# PIDRegler.net
KiCad netlist of a schematic drawn in EAGLE
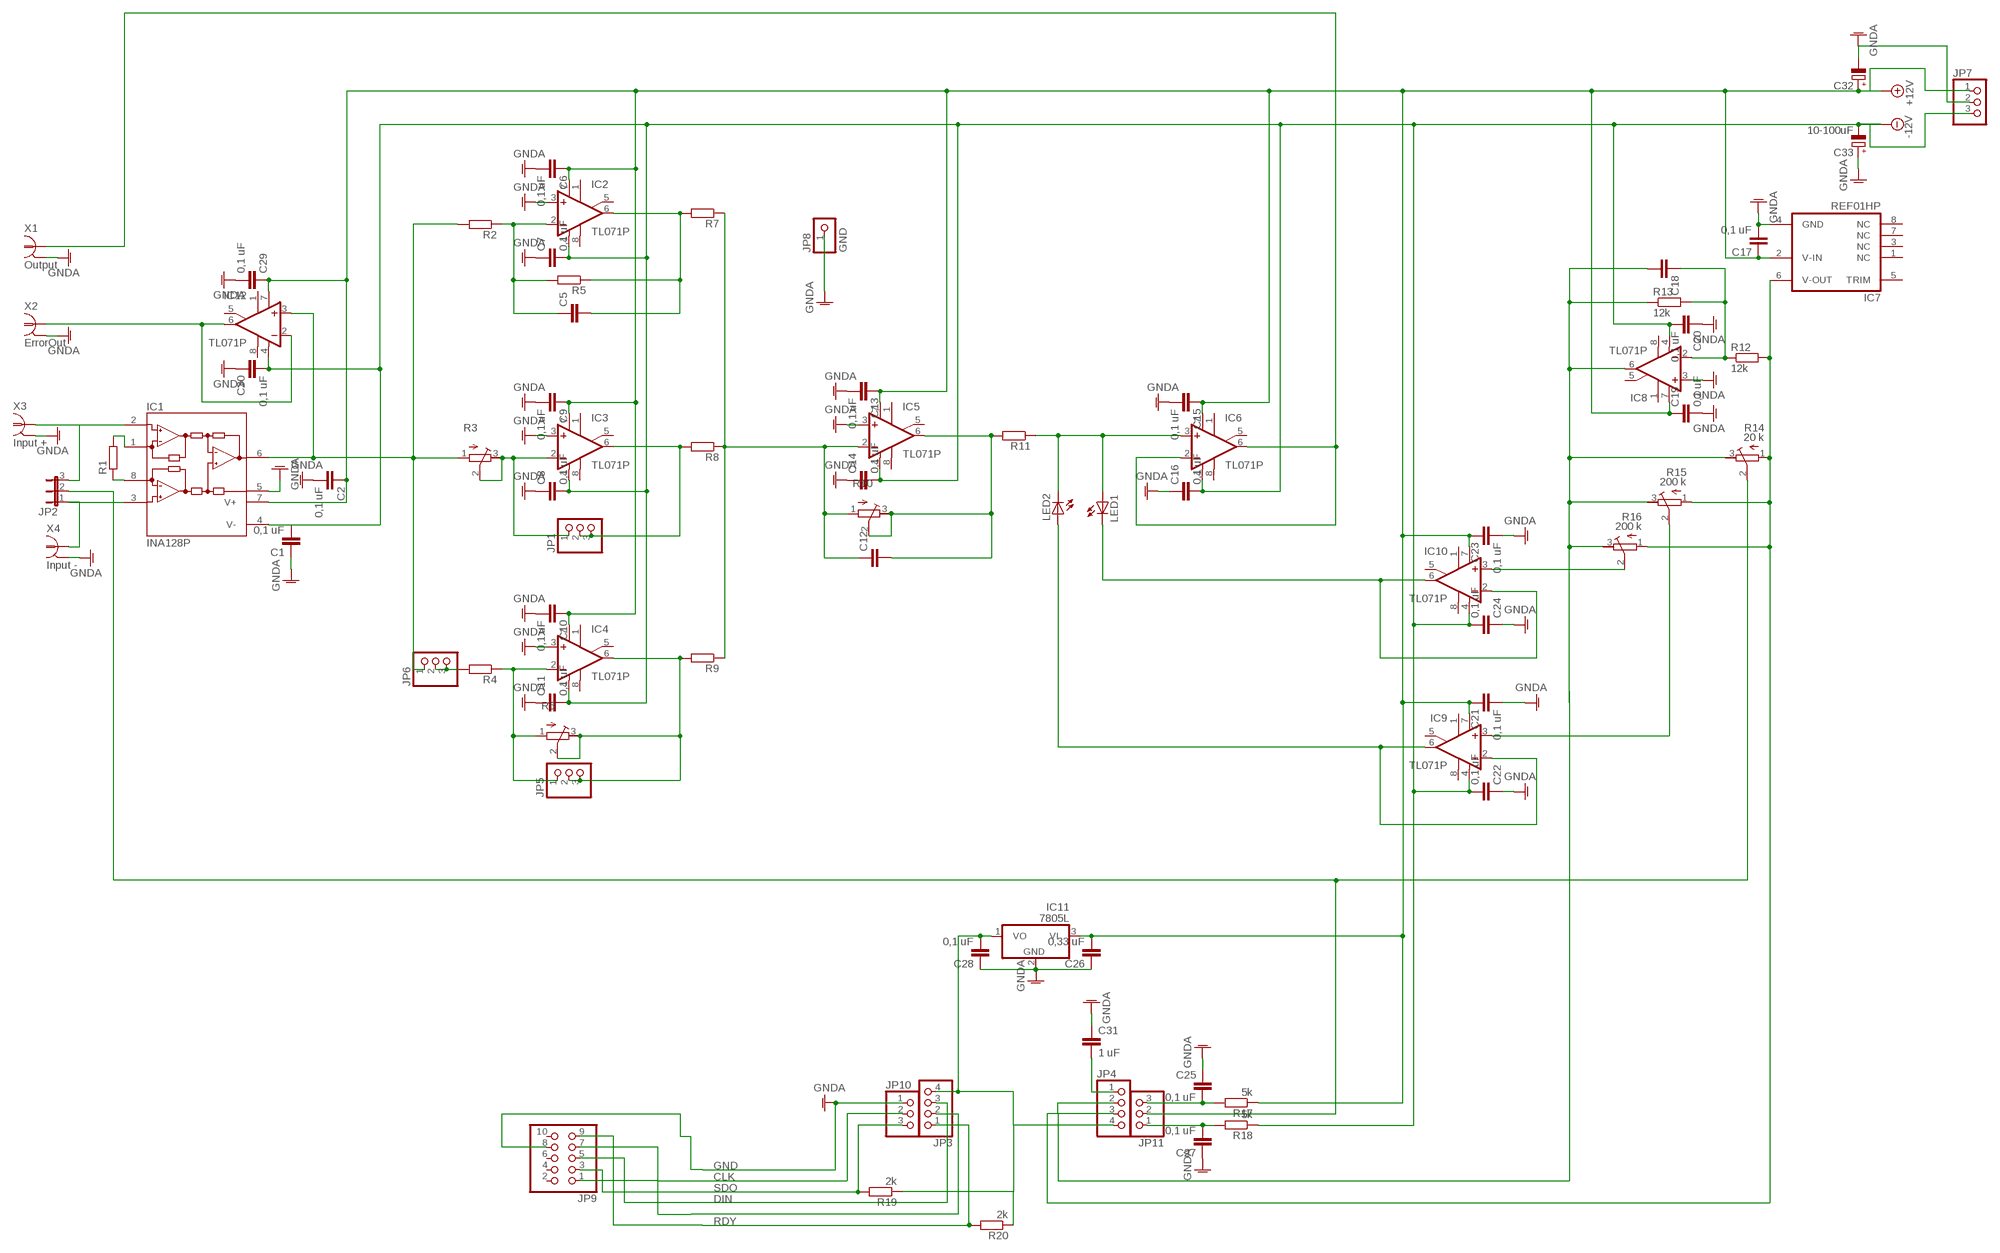
[diagram p0: schematic, sheet 1]

(export (version "E")
  (design (tool "Eeschema 10.0.6"))
  (components
    (comp (ref "C1")
      (value "0,1 uF")
      (footprint "eagle-import:C1206")
      (libsource (lib "eagle-import") (part "C-EUC1206"))
    )
    (comp (ref "C2")
      (value "0,1 uF")
      (footprint "eagle-import:C1206")
      (libsource (lib "eagle-import") (part "C-EUC1206"))
    )
    (comp (ref "C5")
      (value "C-EUC1206")
      (footprint "eagle-import:C1206")
      (libsource (lib "eagle-import") (part "C-EUC1206"))
    )
    (comp (ref "C6")
      (value "0,1 uF")
      (footprint "eagle-import:C1206")
      (libsource (lib "eagle-import") (part "C-EUC1206"))
    )
    (comp (ref "C7")
      (value "0,1 uF")
      (footprint "eagle-import:C1206")
      (libsource (lib "eagle-import") (part "C-EUC1206"))
    )
    (comp (ref "C8")
      (value "0,1 uF")
      (footprint "eagle-import:C1206")
      (libsource (lib "eagle-import") (part "C-EUC1206"))
    )
    (comp (ref "C9")
      (value "0,1 uF")
      (footprint "eagle-import:C1206")
      (libsource (lib "eagle-import") (part "C-EUC1206"))
    )
    (comp (ref "C10")
      (value "0,1 uF")
      (footprint "eagle-import:C1206")
      (libsource (lib "eagle-import") (part "C-EUC1206"))
    )
    (comp (ref "C11")
      (value "0,1 uF")
      (footprint "eagle-import:C1206")
      (libsource (lib "eagle-import") (part "C-EUC1206"))
    )
    (comp (ref "C12")
      (value "C-EUC1206")
      (footprint "eagle-import:C1206")
      (libsource (lib "eagle-import") (part "C-EUC1206"))
    )
    (comp (ref "C13")
      (value "0,1 uF")
      (footprint "eagle-import:C1206")
      (libsource (lib "eagle-import") (part "C-EUC1206"))
    )
    (comp (ref "C14")
      (value "0,1 uF")
      (footprint "eagle-import:C1206")
      (libsource (lib "eagle-import") (part "C-EUC1206"))
    )
    (comp (ref "C15")
      (value "0,1 uF")
      (footprint "eagle-import:C1206")
      (libsource (lib "eagle-import") (part "C-EUC1206"))
    )
    (comp (ref "C16")
      (value "0,1 uF")
      (footprint "eagle-import:C1206")
      (libsource (lib "eagle-import") (part "C-EUC1206"))
    )
    (comp (ref "C17")
      (value "0,1 uF")
      (footprint "eagle-import:C1206")
      (libsource (lib "eagle-import") (part "C-EUC1206"))
    )
    (comp (ref "C18")
      (value "C-EUC1206")
      (footprint "eagle-import:C1206")
      (libsource (lib "eagle-import") (part "C-EUC1206"))
    )
    (comp (ref "C19")
      (value "0,1 uF")
      (footprint "eagle-import:C1206")
      (libsource (lib "eagle-import") (part "C-EUC1206"))
    )
    (comp (ref "C20")
      (value "0,1 uF")
      (footprint "eagle-import:C1206")
      (libsource (lib "eagle-import") (part "C-EUC1206"))
    )
    (comp (ref "C21")
      (value "0,1 uF")
      (footprint "eagle-import:C1206")
      (libsource (lib "eagle-import") (part "C-EUC1206"))
    )
    (comp (ref "C22")
      (value "0,1 uF")
      (footprint "eagle-import:C1206")
      (libsource (lib "eagle-import") (part "C-EUC1206"))
    )
    (comp (ref "C23")
      (value "0,1 uF")
      (footprint "eagle-import:C1206")
      (libsource (lib "eagle-import") (part "C-EUC1206"))
    )
    (comp (ref "C24")
      (value "0,1 uF")
      (footprint "eagle-import:C1206")
      (libsource (lib "eagle-import") (part "C-EUC1206"))
    )
    (comp (ref "C25")
      (value "0,1 uF")
      (footprint "eagle-import:C1206")
      (libsource (lib "eagle-import") (part "C-EUC1206"))
    )
    (comp (ref "C26")
      (value "0,33 uF")
      (footprint "eagle-import:C1206")
      (libsource (lib "eagle-import") (part "C-EUC1206"))
    )
    (comp (ref "C27")
      (value "0,1 uF")
      (footprint "eagle-import:C1206")
      (libsource (lib "eagle-import") (part "C-EUC1206"))
    )
    (comp (ref "C28")
      (value "0,1 uF")
      (footprint "eagle-import:C1206")
      (libsource (lib "eagle-import") (part "C-EUC1206"))
    )
    (comp (ref "C29")
      (value "0,1 uF")
      (footprint "eagle-import:C1206")
      (libsource (lib "eagle-import") (part "C-EUC1206"))
    )
    (comp (ref "C30")
      (value "0,1 uF")
      (footprint "eagle-import:C1206")
      (libsource (lib "eagle-import") (part "C-EUC1206"))
    )
    (comp (ref "C31")
      (value "1 uF")
      (footprint "eagle-import:C1206")
      (libsource (lib "eagle-import") (part "C-EUC1206"))
    )
    (comp (ref "C32")
      (value "CPOL-EUE2.5-6")
      (footprint "eagle-import:E2,5-6")
      (libsource (lib "eagle-import") (part "CPOL-EUE2.5-6"))
    )
    (comp (ref "C33")
      (value "10-100uF")
      (footprint "eagle-import:E2,5-6")
      (libsource (lib "eagle-import") (part "CPOL-EUE2.5-6"))
    )
    (comp (ref "IC1")
      (value "INA128P")
      (footprint "eagle-import:DIL08")
      (fields (field (name "MF") "TEXAS INSTRUMENTS"))
      (libsource (lib "eagle-import") (part "INA128P"))
    )
    (comp (ref "IC2")
      (value "TL071P")
      (footprint "eagle-import:DIL08")
      (libsource (lib "eagle-import") (part "TL071P"))
    )
    (comp (ref "IC3")
      (value "TL071P")
      (footprint "eagle-import:DIL08")
      (libsource (lib "eagle-import") (part "TL071P"))
    )
    (comp (ref "IC4")
      (value "TL071P")
      (footprint "eagle-import:DIL08")
      (libsource (lib "eagle-import") (part "TL071P"))
    )
    (comp (ref "IC5")
      (value "TL071P")
      (footprint "eagle-import:DIL08")
      (libsource (lib "eagle-import") (part "TL071P"))
    )
    (comp (ref "IC6")
      (value "TL071P")
      (footprint "eagle-import:DIL08")
      (libsource (lib "eagle-import") (part "TL071P"))
    )
    (comp (ref "IC7")
      (value "REF01HP")
      (footprint "eagle-import:DIL08")
      (fields (field (name "MF") "ALTERA CORPORATION"))
      (libsource (lib "eagle-import") (part "REF01HP"))
    )
    (comp (ref "IC8")
      (value "TL071P")
      (footprint "eagle-import:DIL08")
      (libsource (lib "eagle-import") (part "TL071P"))
    )
    (comp (ref "IC9")
      (value "TL071P")
      (footprint "eagle-import:DIL08")
      (libsource (lib "eagle-import") (part "TL071P"))
    )
    (comp (ref "IC10")
      (value "TL071P")
      (footprint "eagle-import:DIL08")
      (libsource (lib "eagle-import") (part "TL071P"))
    )
    (comp (ref "IC11")
      (value "7805L")
      (footprint "eagle-import:TO92")
      (libsource (lib "eagle-import") (part "78L05"))
    )
    (comp (ref "IC12")
      (value "TL071P")
      (footprint "eagle-import:DIL08")
      (libsource (lib "eagle-import") (part "TL071P"))
    )
    (comp (ref "JP1")
      (value "PINHD-1X3")
      (footprint "eagle-import:1X03")
      (libsource (lib "eagle-import") (part "PINHD-1X3"))
    )
    (comp (ref "JP2")
      (value "JP2E")
      (footprint "eagle-import:JP2")
      (libsource (lib "eagle-import") (part "JP2E"))
    )
    (comp (ref "JP3")
      (value "PINHD-1X4")
      (footprint "eagle-import:1X04")
      (libsource (lib "eagle-import") (part "PINHD-1X4"))
    )
    (comp (ref "JP4")
      (value "PINHD-1X4")
      (footprint "eagle-import:1X04")
      (libsource (lib "eagle-import") (part "PINHD-1X4"))
    )
    (comp (ref "JP5")
      (value "PINHD-1X3")
      (footprint "eagle-import:1X03")
      (libsource (lib "eagle-import") (part "PINHD-1X3"))
    )
    (comp (ref "JP6")
      (value "PINHD-1X3")
      (footprint "eagle-import:1X03")
      (libsource (lib "eagle-import") (part "PINHD-1X3"))
    )
    (comp (ref "JP7")
      (value "PINHD-1X3")
      (footprint "eagle-import:1X03")
      (libsource (lib "eagle-import") (part "PINHD-1X3"))
    )
    (comp (ref "JP8")
      (value "GND")
      (footprint "eagle-import:1X01")
      (libsource (lib "eagle-import") (part "PINHD-1X1"))
    )
    (comp (ref "JP9")
      (value "PINHD-2X5")
      (footprint "eagle-import:2X05")
      (libsource (lib "eagle-import") (part "PINHD-2X5"))
    )
    (comp (ref "JP10")
      (value "PINHD-1X3")
      (footprint "eagle-import:1X03")
      (libsource (lib "eagle-import") (part "PINHD-1X3"))
    )
    (comp (ref "JP11")
      (value "PINHD-1X3")
      (footprint "eagle-import:1X03")
      (libsource (lib "eagle-import") (part "PINHD-1X3"))
    )
    (comp (ref "LED1")
      (value "LED5MM")
      (footprint "eagle-import:LED5MM")
      (libsource (lib "eagle-import") (part "LED5MM"))
    )
    (comp (ref "LED2")
      (value "LED5MM")
      (footprint "eagle-import:LED5MM")
      (libsource (lib "eagle-import") (part "LED5MM"))
    )
    (comp (ref "R1")
      (value "R-EU_M1206")
      (footprint "eagle-import:M1206")
      (libsource (lib "eagle-import") (part "R-EU_M1206"))
    )
    (comp (ref "R2")
      (value "R-EU_M1206")
      (footprint "eagle-import:M1206")
      (libsource (lib "eagle-import") (part "R-EU_M1206"))
    )
    (comp (ref "R3")
      (value "R-TRIMM64X")
      (footprint "eagle-import:RTRIM64X")
      (libsource (lib "eagle-import") (part "R-TRIMM64X"))
    )
    (comp (ref "R4")
      (value "R-EU_M1206")
      (footprint "eagle-import:M1206")
      (libsource (lib "eagle-import") (part "R-EU_M1206"))
    )
    (comp (ref "R5")
      (value "R-EU_M1206")
      (footprint "eagle-import:M1206")
      (libsource (lib "eagle-import") (part "R-EU_M1206"))
    )
    (comp (ref "R6")
      (value "R-TRIMM64X")
      (footprint "eagle-import:RTRIM64X")
      (libsource (lib "eagle-import") (part "R-TRIMM64X"))
    )
    (comp (ref "R7")
      (value "R-EU_M1206")
      (footprint "eagle-import:M1206")
      (libsource (lib "eagle-import") (part "R-EU_M1206"))
    )
    (comp (ref "R8")
      (value "R-EU_M1206")
      (footprint "eagle-import:M1206")
      (libsource (lib "eagle-import") (part "R-EU_M1206"))
    )
    (comp (ref "R9")
      (value "R-EU_M1206")
      (footprint "eagle-import:M1206")
      (libsource (lib "eagle-import") (part "R-EU_M1206"))
    )
    (comp (ref "R10")
      (value "R-TRIMM64X")
      (footprint "eagle-import:RTRIM64X")
      (libsource (lib "eagle-import") (part "R-TRIMM64X"))
    )
    (comp (ref "R11")
      (value "R-EU_M1206")
      (footprint "eagle-import:M1206")
      (libsource (lib "eagle-import") (part "R-EU_M1206"))
    )
    (comp (ref "R12")
      (value "12k")
      (footprint "eagle-import:M1206")
      (libsource (lib "eagle-import") (part "R-EU_M1206"))
    )
    (comp (ref "R13")
      (value "12k")
      (footprint "eagle-import:M1206")
      (libsource (lib "eagle-import") (part "R-EU_M1206"))
    )
    (comp (ref "R14")
      (value "20 k")
      (footprint "eagle-import:RTRIM64X")
      (libsource (lib "eagle-import") (part "R-TRIMM64X"))
    )
    (comp (ref "R15")
      (value "200 k")
      (footprint "eagle-import:RTRIM64X")
      (libsource (lib "eagle-import") (part "R-TRIMM64X"))
    )
    (comp (ref "R16")
      (value "200 k")
      (footprint "eagle-import:RTRIM64X")
      (libsource (lib "eagle-import") (part "R-TRIMM64X"))
    )
    (comp (ref "R17")
      (value "5k")
      (footprint "eagle-import:M1206")
      (libsource (lib "eagle-import") (part "R-EU_M1206"))
    )
    (comp (ref "R18")
      (value "5k")
      (footprint "eagle-import:M1206")
      (libsource (lib "eagle-import") (part "R-EU_M1206"))
    )
    (comp (ref "R19")
      (value "2k")
      (footprint "eagle-import:M1206")
      (libsource (lib "eagle-import") (part "R-EU_M1206"))
    )
    (comp (ref "R20")
      (value "2k")
      (footprint "eagle-import:M1206")
      (libsource (lib "eagle-import") (part "R-EU_M1206"))
    )
    (comp (ref "X1")
      (value "Output")
      (footprint "eagle-import:AMP_227161")
      (fields (field (name "MF") "TYCO ELECTRONICS") (field (name "MPN") "1-227161"))
      (libsource (lib "eagle-import") (part "?2271611--0"))
    )
    (comp (ref "X2")
      (value "ErrorOut")
      (footprint "eagle-import:AMP_227161")
      (fields (field (name "MF") "TYCO ELECTRONICS") (field (name "MPN") "1-227161"))
      (libsource (lib "eagle-import") (part "?2271611--0"))
    )
    (comp (ref "X3")
      (value "Input +")
      (footprint "eagle-import:AMP_227161")
      (fields (field (name "MF") "TYCO ELECTRONICS") (field (name "MPN") "1-227161"))
      (libsource (lib "eagle-import") (part "?2271611--0"))
    )
    (comp (ref "X4")
      (value "Input -")
      (footprint "eagle-import:AMP_227161")
      (fields (field (name "MF") "TYCO ELECTRONICS") (field (name "MPN") "1-227161"))
      (libsource (lib "eagle-import") (part "?2271611--0"))
    )
  )
  (nets
    (net (code "1") (name "+12V") (class "Default")
      (node (ref "C10") (pin "1") (pinfunction "1_1") (pintype "passive"))
      (node (ref "C13") (pin "1") (pinfunction "1_1") (pintype "passive"))
      (node (ref "C15") (pin "1") (pinfunction "1_1") (pintype "passive"))
      (node (ref "C17") (pin "1") (pinfunction "1_1") (pintype "passive"))
      (node (ref "C19") (pin "1") (pinfunction "1_1") (pintype "passive"))
      (node (ref "C2") (pin "1") (pinfunction "1_1") (pintype "passive"))
      (node (ref "C21") (pin "1") (pinfunction "1_1") (pintype "passive"))
      (node (ref "C23") (pin "1") (pinfunction "1_1") (pintype "passive"))
      (node (ref "C26") (pin "2") (pinfunction "2_2") (pintype "passive"))
      (node (ref "C29") (pin "1") (pinfunction "1_1") (pintype "passive"))
      (node (ref "C32") (pin "+") (pinfunction "+_+") (pintype "passive"))
      (node (ref "C6") (pin "1") (pinfunction "1_1") (pintype "passive"))
      (node (ref "C9") (pin "1") (pinfunction "1_1") (pintype "passive"))
      (node (ref "IC1") (pin "7") (pinfunction "V+_7") (pintype "power_in"))
      (node (ref "IC10") (pin "7") (pinfunction "V+_7") (pintype "power_in"))
      (node (ref "IC11") (pin "3") (pinfunction "VI_3") (pintype "input"))
      (node (ref "IC12") (pin "7") (pinfunction "V+_7") (pintype "power_in"))
      (node (ref "IC2") (pin "7") (pinfunction "V+_7") (pintype "power_in"))
      (node (ref "IC3") (pin "7") (pinfunction "V+_7") (pintype "power_in"))
      (node (ref "IC4") (pin "7") (pinfunction "V+_7") (pintype "power_in"))
      (node (ref "IC5") (pin "7") (pinfunction "V+_7") (pintype "power_in"))
      (node (ref "IC6") (pin "7") (pinfunction "V+_7") (pintype "power_in"))
      (node (ref "IC7") (pin "2") (pinfunction "V-IN_2") (pintype "power_in"))
      (node (ref "IC8") (pin "7") (pinfunction "V+_7") (pintype "power_in"))
      (node (ref "IC9") (pin "7") (pinfunction "V+_7") (pintype "power_in"))
      (node (ref "JP7") (pin "1") (pinfunction "1_1") (pintype "passive"))
      (node (ref "R17") (pin "1") (pinfunction "1_1") (pintype "passive"))
    )
    (net (code "2") (name "-12V") (class "Default")
      (node (ref "C1") (pin "2") (pinfunction "2_2") (pintype "passive"))
      (node (ref "C11") (pin "2") (pinfunction "2_2") (pintype "passive"))
      (node (ref "C14") (pin "2") (pinfunction "2_2") (pintype "passive"))
      (node (ref "C16") (pin "2") (pinfunction "2_2") (pintype "passive"))
      (node (ref "C20") (pin "2") (pinfunction "2_2") (pintype "passive"))
      (node (ref "C22") (pin "2") (pinfunction "2_2") (pintype "passive"))
      (node (ref "C24") (pin "2") (pinfunction "2_2") (pintype "passive"))
      (node (ref "C30") (pin "2") (pinfunction "2_2") (pintype "passive"))
      (node (ref "C33") (pin "-") (pinfunction "-_-") (pintype "passive"))
      (node (ref "C7") (pin "2") (pinfunction "2_2") (pintype "passive"))
      (node (ref "C8") (pin "2") (pinfunction "2_2") (pintype "passive"))
      (node (ref "IC1") (pin "4") (pinfunction "V-_4") (pintype "power_in"))
      (node (ref "IC10") (pin "4") (pinfunction "V-_4") (pintype "power_in"))
      (node (ref "IC12") (pin "4") (pinfunction "V-_4") (pintype "power_in"))
      (node (ref "IC2") (pin "4") (pinfunction "V-_4") (pintype "power_in"))
      (node (ref "IC3") (pin "4") (pinfunction "V-_4") (pintype "power_in"))
      (node (ref "IC4") (pin "4") (pinfunction "V-_4") (pintype "power_in"))
      (node (ref "IC5") (pin "4") (pinfunction "V-_4") (pintype "power_in"))
      (node (ref "IC6") (pin "4") (pinfunction "V-_4") (pintype "power_in"))
      (node (ref "IC8") (pin "4") (pinfunction "V-_4") (pintype "power_in"))
      (node (ref "IC9") (pin "4") (pinfunction "V-_4") (pintype "power_in"))
      (node (ref "JP7") (pin "3") (pinfunction "3_3") (pintype "passive"))
      (node (ref "R18") (pin "1") (pinfunction "1_1") (pintype "passive"))
    )
    (net (code "3") (name "/CLK") (class "Default")
      (node (ref "JP10") (pin "2") (pinfunction "2_2") (pintype "passive"))
      (node (ref "JP9") (pin "1") (pinfunction "1_1") (pintype "passive"))
    )
    (net (code "4") (name "/DIN") (class "Default")
      (node (ref "JP3") (pin "3") (pinfunction "3_3") (pintype "passive"))
      (node (ref "JP9") (pin "5") (pinfunction "5_5") (pintype "passive"))
    )
    (net (code "5") (name "/RDY") (class "Default")
      (node (ref "JP3") (pin "1") (pinfunction "1_1") (pintype "passive"))
      (node (ref "JP9") (pin "9") (pinfunction "9_9") (pintype "passive"))
      (node (ref "R20") (pin "2") (pinfunction "2_2") (pintype "passive"))
    )
    (net (code "6") (name "/SDO") (class "Default")
      (node (ref "JP10") (pin "3") (pinfunction "3_3") (pintype "passive"))
      (node (ref "JP9") (pin "3") (pinfunction "3_3") (pintype "passive"))
      (node (ref "R19") (pin "2") (pinfunction "2_2") (pintype "passive"))
    )
    (net (code "7") (name "GNDA") (class "Default")
      (node (ref "C1") (pin "1") (pinfunction "1_1") (pintype "passive"))
      (node (ref "C10") (pin "2") (pinfunction "2_2") (pintype "passive"))
      (node (ref "C11") (pin "1") (pinfunction "1_1") (pintype "passive"))
      (node (ref "C13") (pin "2") (pinfunction "2_2") (pintype "passive"))
      (node (ref "C14") (pin "1") (pinfunction "1_1") (pintype "passive"))
      (node (ref "C15") (pin "2") (pinfunction "2_2") (pintype "passive"))
      (node (ref "C16") (pin "1") (pinfunction "1_1") (pintype "passive"))
      (node (ref "C17") (pin "2") (pinfunction "2_2") (pintype "passive"))
      (node (ref "C19") (pin "2") (pinfunction "2_2") (pintype "passive"))
      (node (ref "C2") (pin "2") (pinfunction "2_2") (pintype "passive"))
      (node (ref "C20") (pin "1") (pinfunction "1_1") (pintype "passive"))
      (node (ref "C21") (pin "2") (pinfunction "2_2") (pintype "passive"))
      (node (ref "C22") (pin "1") (pinfunction "1_1") (pintype "passive"))
      (node (ref "C23") (pin "2") (pinfunction "2_2") (pintype "passive"))
      (node (ref "C24") (pin "1") (pinfunction "1_1") (pintype "passive"))
      (node (ref "C25") (pin "1") (pinfunction "1_1") (pintype "passive"))
      (node (ref "C26") (pin "1") (pinfunction "1_1") (pintype "passive"))
      (node (ref "C27") (pin "1") (pinfunction "1_1") (pintype "passive"))
      (node (ref "C28") (pin "1") (pinfunction "1_1") (pintype "passive"))
      (node (ref "C29") (pin "2") (pinfunction "2_2") (pintype "passive"))
      (node (ref "C30") (pin "1") (pinfunction "1_1") (pintype "passive"))
      (node (ref "C31") (pin "1") (pinfunction "1_1") (pintype "passive"))
      (node (ref "C32") (pin "-") (pinfunction "-_-") (pintype "passive"))
      (node (ref "C33") (pin "+") (pinfunction "+_+") (pintype "passive"))
      (node (ref "C6") (pin "2") (pinfunction "2_2") (pintype "passive"))
      (node (ref "C7") (pin "1") (pinfunction "1_1") (pintype "passive"))
      (node (ref "C8") (pin "1") (pinfunction "1_1") (pintype "passive"))
      (node (ref "C9") (pin "2") (pinfunction "2_2") (pintype "passive"))
      (node (ref "IC1") (pin "5") (pinfunction "REF_5") (pintype "passive"))
      (node (ref "IC11") (pin "2") (pinfunction "GND_2") (pintype "passive"))
      (node (ref "IC2") (pin "3") (pinfunction "+IN_3") (pintype "input"))
      (node (ref "IC3") (pin "3") (pinfunction "+IN_3") (pintype "input"))
      (node (ref "IC4") (pin "3") (pinfunction "+IN_3") (pintype "input"))
      (node (ref "IC5") (pin "3") (pinfunction "+IN_3") (pintype "input"))
      (node (ref "IC7") (pin "4") (pinfunction "GND_4") (pintype "power_in"))
      (node (ref "IC8") (pin "3") (pinfunction "+IN_3") (pintype "input"))
      (node (ref "JP10") (pin "1") (pinfunction "1_1") (pintype "passive"))
      (node (ref "JP7") (pin "2") (pinfunction "2_2") (pintype "passive"))
      (node (ref "JP8") (pin "1") (pinfunction "1_1") (pintype "passive"))
      (node (ref "JP9") (pin "8") (pinfunction "8_8") (pintype "passive"))
      (node (ref "X1") (pin "2") (pinfunction "GND_2") (pintype "power_in"))
      (node (ref "X2") (pin "2") (pinfunction "GND_2") (pintype "power_in"))
      (node (ref "X3") (pin "2") (pinfunction "GND_2") (pintype "power_in"))
      (node (ref "X4") (pin "2") (pinfunction "GND_2") (pintype "power_in"))
    )
    (net (code "8") (name "Net-(C25-Pad2)") (class "Default")
      (node (ref "C25") (pin "2") (pinfunction "2_2") (pintype "passive"))
      (node (ref "JP11") (pin "3") (pinfunction "3_3") (pintype "passive"))
      (node (ref "R17") (pin "2") (pinfunction "2_2") (pintype "passive"))
    )
    (net (code "9") (name "Net-(C27-Pad2)") (class "Default")
      (node (ref "C27") (pin "2") (pinfunction "2_2") (pintype "passive"))
      (node (ref "JP11") (pin "1") (pinfunction "1_1") (pintype "passive"))
      (node (ref "R18") (pin "2") (pinfunction "2_2") (pintype "passive"))
    )
    (net (code "10") (name "Net-(C31-Pad2)") (class "Default")
      (node (ref "C31") (pin "2") (pinfunction "2_2") (pintype "passive"))
      (node (ref "JP4") (pin "1") (pinfunction "1_1") (pintype "passive"))
    )
    (net (code "11") (name "Net-(IC1-+IN)") (class "Default")
      (node (ref "IC1") (pin "3") (pinfunction "+IN_3") (pintype "input"))
      (node (ref "JP2") (pin "1") (pinfunction "1_1") (pintype "passive"))
      (node (ref "X4") (pin "1") (pinfunction "1_1") (pintype "passive"))
    )
    (net (code "12") (name "Net-(IC1--IN)") (class "Default")
      (node (ref "IC1") (pin "2") (pinfunction "-IN_2") (pintype "input"))
      (node (ref "JP2") (pin "3") (pinfunction "3_3") (pintype "passive"))
      (node (ref "X3") (pin "1") (pinfunction "1_1") (pintype "passive"))
    )
    (net (code "13") (name "Net-(IC1-OUT)") (class "Default")
      (node (ref "IC1") (pin "6") (pinfunction "OUT_6") (pintype "output"))
      (node (ref "IC12") (pin "3") (pinfunction "+IN_3") (pintype "input"))
      (node (ref "JP6") (pin "1") (pinfunction "1_1") (pintype "passive"))
      (node (ref "R2") (pin "2") (pinfunction "2_2") (pintype "passive"))
      (node (ref "R3") (pin "1") (pinfunction "E_1") (pintype "passive"))
    )
    (net (code "14") (name "Net-(IC1-RG-Pad1)") (class "Default")
      (node (ref "IC1") (pin "1") (pinfunction "RG_1") (pintype "passive"))
      (node (ref "R1") (pin "2") (pinfunction "2_2") (pintype "passive"))
    )
    (net (code "15") (name "Net-(IC1-RG-Pad8)") (class "Default")
      (node (ref "IC1") (pin "8") (pinfunction "RG_8") (pintype "passive"))
      (node (ref "R1") (pin "1") (pinfunction "1_1") (pintype "passive"))
    )
    (net (code "16") (name "Net-(IC2--IN)") (class "Default")
      (node (ref "C5") (pin "1") (pinfunction "1_1") (pintype "passive"))
      (node (ref "IC2") (pin "2") (pinfunction "-IN_2") (pintype "input"))
      (node (ref "R2") (pin "1") (pinfunction "1_1") (pintype "passive"))
      (node (ref "R5") (pin "2") (pinfunction "2_2") (pintype "passive"))
    )
    (net (code "17") (name "Net-(IC2-OUT)") (class "Default")
      (node (ref "C5") (pin "2") (pinfunction "2_2") (pintype "passive"))
      (node (ref "IC2") (pin "6") (pinfunction "OUT_6") (pintype "output"))
      (node (ref "R5") (pin "1") (pinfunction "1_1") (pintype "passive"))
      (node (ref "R7") (pin "2") (pinfunction "2_2") (pintype "passive"))
    )
    (net (code "18") (name "Net-(IC3--IN)") (class "Default")
      (node (ref "IC3") (pin "2") (pinfunction "-IN_2") (pintype "input"))
      (node (ref "JP1") (pin "1") (pinfunction "1_1") (pintype "passive"))
      (node (ref "R3") (pin "2") (pinfunction "S_2") (pintype "passive"))
      (node (ref "R3") (pin "3") (pinfunction "A_3") (pintype "passive"))
    )
    (net (code "19") (name "Net-(IC3-OUT)") (class "Default")
      (node (ref "IC3") (pin "6") (pinfunction "OUT_6") (pintype "output"))
      (node (ref "JP1") (pin "2") (pinfunction "2_2") (pintype "passive"))
      (node (ref "JP1") (pin "3") (pinfunction "3_3") (pintype "passive"))
      (node (ref "R8") (pin "2") (pinfunction "2_2") (pintype "passive"))
    )
    (net (code "20") (name "Net-(IC4--IN)") (class "Default")
      (node (ref "IC4") (pin "2") (pinfunction "-IN_2") (pintype "input"))
      (node (ref "JP5") (pin "1") (pinfunction "1_1") (pintype "passive"))
      (node (ref "R4") (pin "1") (pinfunction "1_1") (pintype "passive"))
      (node (ref "R6") (pin "1") (pinfunction "E_1") (pintype "passive"))
    )
    (net (code "21") (name "Net-(IC4-OUT)") (class "Default")
      (node (ref "IC4") (pin "6") (pinfunction "OUT_6") (pintype "output"))
      (node (ref "JP5") (pin "2") (pinfunction "2_2") (pintype "passive"))
      (node (ref "JP5") (pin "3") (pinfunction "3_3") (pintype "passive"))
      (node (ref "R6") (pin "2") (pinfunction "S_2") (pintype "passive"))
      (node (ref "R6") (pin "3") (pinfunction "A_3") (pintype "passive"))
      (node (ref "R9") (pin "2") (pinfunction "2_2") (pintype "passive"))
    )
    (net (code "22") (name "Net-(IC5--IN)") (class "Default")
      (node (ref "C12") (pin "1") (pinfunction "1_1") (pintype "passive"))
      (node (ref "IC5") (pin "2") (pinfunction "-IN_2") (pintype "input"))
      (node (ref "R10") (pin "1") (pinfunction "E_1") (pintype "passive"))
      (node (ref "R7") (pin "1") (pinfunction "1_1") (pintype "passive"))
      (node (ref "R8") (pin "1") (pinfunction "1_1") (pintype "passive"))
      (node (ref "R9") (pin "1") (pinfunction "1_1") (pintype "passive"))
    )
    (net (code "23") (name "Net-(IC5-OUT)") (class "Default")
      (node (ref "C12") (pin "2") (pinfunction "2_2") (pintype "passive"))
      (node (ref "IC5") (pin "6") (pinfunction "OUT_6") (pintype "output"))
      (node (ref "R10") (pin "2") (pinfunction "S_2") (pintype "passive"))
      (node (ref "R10") (pin "3") (pinfunction "A_3") (pintype "passive"))
      (node (ref "R11") (pin "2") (pinfunction "2_2") (pintype "passive"))
    )
    (net (code "24") (name "Net-(IC6-+IN)") (class "Default")
      (node (ref "IC6") (pin "3") (pinfunction "+IN_3") (pintype "input"))
      (node (ref "LED1") (pin "A") (pinfunction "A_A") (pintype "passive"))
      (node (ref "LED2") (pin "K") (pinfunction "C_K") (pintype "passive"))
      (node (ref "R11") (pin "1") (pinfunction "1_1") (pintype "passive"))
    )
    (net (code "25") (name "Net-(IC6--IN)") (class "Default")
      (node (ref "IC6") (pin "2") (pinfunction "-IN_2") (pintype "input"))
      (node (ref "IC6") (pin "6") (pinfunction "OUT_6") (pintype "output"))
      (node (ref "X1") (pin "1") (pinfunction "1_1") (pintype "passive"))
    )
    (net (code "26") (name "Net-(IC7-V-OUT)") (class "Default")
      (node (ref "IC7") (pin "6") (pinfunction "V-OUT_6") (pintype "output"))
      (node (ref "JP4") (pin "3") (pinfunction "3_3") (pintype "passive"))
      (node (ref "R12") (pin "2") (pinfunction "2_2") (pintype "passive"))
      (node (ref "R14") (pin "1") (pinfunction "E_1") (pintype "passive"))
      (node (ref "R15") (pin "1") (pinfunction "E_1") (pintype "passive"))
      (node (ref "R16") (pin "1") (pinfunction "E_1") (pintype "passive"))
    )
    (net (code "27") (name "Net-(IC8--IN)") (class "Default")
      (node (ref "C18") (pin "1") (pinfunction "1_1") (pintype "passive"))
      (node (ref "IC8") (pin "2") (pinfunction "-IN_2") (pintype "input"))
      (node (ref "R12") (pin "1") (pinfunction "1_1") (pintype "passive"))
      (node (ref "R13") (pin "2") (pinfunction "2_2") (pintype "passive"))
    )
    (net (code "28") (name "Net-(IC8-OUT)") (class "Default")
      (node (ref "C18") (pin "2") (pinfunction "2_2") (pintype "passive"))
      (node (ref "IC8") (pin "6") (pinfunction "OUT_6") (pintype "output"))
      (node (ref "JP4") (pin "2") (pinfunction "2_2") (pintype "passive"))
      (node (ref "R13") (pin "1") (pinfunction "1_1") (pintype "passive"))
      (node (ref "R14") (pin "3") (pinfunction "A_3") (pintype "passive"))
      (node (ref "R15") (pin "3") (pinfunction "A_3") (pintype "passive"))
      (node (ref "R16") (pin "3") (pinfunction "A_3") (pintype "passive"))
    )
    (net (code "29") (name "Net-(IC9-+IN)") (class "Default")
      (node (ref "IC9") (pin "3") (pinfunction "+IN_3") (pintype "input"))
      (node (ref "R15") (pin "2") (pinfunction "S_2") (pintype "passive"))
    )
    (net (code "30") (name "Net-(IC9--IN)") (class "Default")
      (node (ref "IC9") (pin "2") (pinfunction "-IN_2") (pintype "input"))
      (node (ref "IC9") (pin "6") (pinfunction "OUT_6") (pintype "output"))
      (node (ref "LED2") (pin "A") (pinfunction "A_A") (pintype "passive"))
    )
    (net (code "31") (name "Net-(IC10-+IN)") (class "Default")
      (node (ref "IC10") (pin "3") (pinfunction "+IN_3") (pintype "input"))
      (node (ref "R16") (pin "2") (pinfunction "S_2") (pintype "passive"))
    )
    (net (code "32") (name "Net-(IC10--IN)") (class "Default")
      (node (ref "IC10") (pin "2") (pinfunction "-IN_2") (pintype "input"))
      (node (ref "IC10") (pin "6") (pinfunction "OUT_6") (pintype "output"))
      (node (ref "LED1") (pin "K") (pinfunction "C_K") (pintype "passive"))
    )
    (net (code "33") (name "Net-(IC11-VO)") (class "Default")
      (node (ref "C28") (pin "2") (pinfunction "2_2") (pintype "passive"))
      (node (ref "IC11") (pin "1") (pinfunction "VO_1") (pintype "passive"))
      (node (ref "JP3") (pin "4") (pinfunction "4_4") (pintype "passive"))
      (node (ref "JP4") (pin "4") (pinfunction "4_4") (pintype "passive"))
      (node (ref "R19") (pin "1") (pinfunction "1_1") (pintype "passive"))
      (node (ref "R20") (pin "1") (pinfunction "1_1") (pintype "passive"))
    )
    (net (code "34") (name "Net-(IC12--IN)") (class "Default")
      (node (ref "IC12") (pin "2") (pinfunction "-IN_2") (pintype "input"))
      (node (ref "IC12") (pin "6") (pinfunction "OUT_6") (pintype "output"))
      (node (ref "X2") (pin "1") (pinfunction "1_1") (pintype "passive"))
    )
    (net (code "35") (name "Net-(JP3-Pad2)") (class "Default")
      (node (ref "JP3") (pin "2") (pinfunction "2_2") (pintype "passive"))
      (node (ref "JP9") (pin "7") (pinfunction "7_7") (pintype "passive"))
    )
    (net (code "36") (name "Net-(JP6-Pad2)") (class "Default")
      (node (ref "JP6") (pin "2") (pinfunction "2_2") (pintype "passive"))
      (node (ref "JP6") (pin "3") (pinfunction "3_3") (pintype "passive"))
      (node (ref "R4") (pin "2") (pinfunction "2_2") (pintype "passive"))
    )
    (net (code "37") (name "Net-(R14-S)") (class "Default")
      (node (ref "JP11") (pin "2") (pinfunction "2_2") (pintype "passive"))
      (node (ref "JP2") (pin "2") (pinfunction "2_2") (pintype "passive"))
      (node (ref "R14") (pin "2") (pinfunction "S_2") (pintype "passive"))
    )
    (net (code "38") (name "unconnected-(IC2-ON1-Pad1)") (class "Default")
      (node (ref "IC2") (pin "1") (pinfunction "ON1_1") (pintype "passive"))
    )
    (net (code "39") (name "unconnected-(IC2-ON2-Pad5)") (class "Default")
      (node (ref "IC2") (pin "5") (pinfunction "ON2_5") (pintype "passive"))
    )
    (net (code "40") (name "unconnected-(IC2-OPT-Pad8)") (class "Default")
      (node (ref "IC2") (pin "8") (pinfunction "OPT_8") (pintype "passive"))
    )
    (net (code "41") (name "unconnected-(IC3-ON1-Pad1)") (class "Default")
      (node (ref "IC3") (pin "1") (pinfunction "ON1_1") (pintype "passive"))
    )
    (net (code "42") (name "unconnected-(IC3-ON2-Pad5)") (class "Default")
      (node (ref "IC3") (pin "5") (pinfunction "ON2_5") (pintype "passive"))
    )
    (net (code "43") (name "unconnected-(IC3-OPT-Pad8)") (class "Default")
      (node (ref "IC3") (pin "8") (pinfunction "OPT_8") (pintype "passive"))
    )
    (net (code "44") (name "unconnected-(IC4-ON1-Pad1)") (class "Default")
      (node (ref "IC4") (pin "1") (pinfunction "ON1_1") (pintype "passive"))
    )
    (net (code "45") (name "unconnected-(IC4-ON2-Pad5)") (class "Default")
      (node (ref "IC4") (pin "5") (pinfunction "ON2_5") (pintype "passive"))
    )
    (net (code "46") (name "unconnected-(IC4-OPT-Pad8)") (class "Default")
      (node (ref "IC4") (pin "8") (pinfunction "OPT_8") (pintype "passive"))
    )
    (net (code "47") (name "unconnected-(IC5-ON1-Pad1)") (class "Default")
      (node (ref "IC5") (pin "1") (pinfunction "ON1_1") (pintype "passive"))
    )
    (net (code "48") (name "unconnected-(IC5-ON2-Pad5)") (class "Default")
      (node (ref "IC5") (pin "5") (pinfunction "ON2_5") (pintype "passive"))
    )
    (net (code "49") (name "unconnected-(IC5-OPT-Pad8)") (class "Default")
      (node (ref "IC5") (pin "8") (pinfunction "OPT_8") (pintype "passive"))
    )
    (net (code "50") (name "unconnected-(IC6-ON1-Pad1)") (class "Default")
      (node (ref "IC6") (pin "1") (pinfunction "ON1_1") (pintype "passive"))
    )
    (net (code "51") (name "unconnected-(IC6-ON2-Pad5)") (class "Default")
      (node (ref "IC6") (pin "5") (pinfunction "ON2_5") (pintype "passive"))
    )
    (net (code "52") (name "unconnected-(IC6-OPT-Pad8)") (class "Default")
      (node (ref "IC6") (pin "8") (pinfunction "OPT_8") (pintype "passive"))
    )
    (net (code "53") (name "unconnected-(IC7-NC-Pad1)") (class "Default")
      (node (ref "IC7") (pin "1") (pinfunction "NC_1") (pintype "no_connect"))
    )
    (net (code "54") (name "unconnected-(IC7-NC-Pad3)") (class "Default")
      (node (ref "IC7") (pin "3") (pinfunction "NC_3") (pintype "no_connect"))
    )
    (net (code "55") (name "unconnected-(IC7-NC-Pad7)") (class "Default")
      (node (ref "IC7") (pin "7") (pinfunction "NC_7") (pintype "no_connect"))
    )
    (net (code "56") (name "unconnected-(IC7-NC-Pad8)") (class "Default")
      (node (ref "IC7") (pin "8") (pinfunction "NC_8") (pintype "no_connect"))
    )
    (net (code "57") (name "unconnected-(IC7-TRIM-Pad5)") (class "Default")
      (node (ref "IC7") (pin "5") (pinfunction "TRIM_5") (pintype "input"))
    )
    (net (code "58") (name "unconnected-(IC8-ON1-Pad1)") (class "Default")
      (node (ref "IC8") (pin "1") (pinfunction "ON1_1") (pintype "passive"))
    )
    (net (code "59") (name "unconnected-(IC8-ON2-Pad5)") (class "Default")
      (node (ref "IC8") (pin "5") (pinfunction "ON2_5") (pintype "passive"))
    )
    (net (code "60") (name "unconnected-(IC8-OPT-Pad8)") (class "Default")
      (node (ref "IC8") (pin "8") (pinfunction "OPT_8") (pintype "passive"))
    )
    (net (code "61") (name "unconnected-(IC9-ON1-Pad1)") (class "Default")
      (node (ref "IC9") (pin "1") (pinfunction "ON1_1") (pintype "passive"))
    )
    (net (code "62") (name "unconnected-(IC9-ON2-Pad5)") (class "Default")
      (node (ref "IC9") (pin "5") (pinfunction "ON2_5") (pintype "passive"))
    )
    (net (code "63") (name "unconnected-(IC9-OPT-Pad8)") (class "Default")
      (node (ref "IC9") (pin "8") (pinfunction "OPT_8") (pintype "passive"))
    )
    (net (code "64") (name "unconnected-(IC10-ON1-Pad1)") (class "Default")
      (node (ref "IC10") (pin "1") (pinfunction "ON1_1") (pintype "passive"))
    )
    (net (code "65") (name "unconnected-(IC10-ON2-Pad5)") (class "Default")
      (node (ref "IC10") (pin "5") (pinfunction "ON2_5") (pintype "passive"))
    )
    (net (code "66") (name "unconnected-(IC10-OPT-Pad8)") (class "Default")
      (node (ref "IC10") (pin "8") (pinfunction "OPT_8") (pintype "passive"))
    )
    (net (code "67") (name "unconnected-(IC12-ON1-Pad1)") (class "Default")
      (node (ref "IC12") (pin "1") (pinfunction "ON1_1") (pintype "passive"))
    )
    (net (code "68") (name "unconnected-(IC12-ON2-Pad5)") (class "Default")
      (node (ref "IC12") (pin "5") (pinfunction "ON2_5") (pintype "passive"))
    )
    (net (code "69") (name "unconnected-(IC12-OPT-Pad8)") (class "Default")
      (node (ref "IC12") (pin "8") (pinfunction "OPT_8") (pintype "passive"))
    )
    (net (code "70") (name "unconnected-(JP9-Pad2)") (class "Default")
      (node (ref "JP9") (pin "2") (pinfunction "2_2") (pintype "passive"))
    )
    (net (code "71") (name "unconnected-(JP9-Pad4)") (class "Default")
      (node (ref "JP9") (pin "4") (pinfunction "4_4") (pintype "passive"))
    )
    (net (code "72") (name "unconnected-(JP9-Pad6)") (class "Default")
      (node (ref "JP9") (pin "6") (pinfunction "6_6") (pintype "passive"))
    )
    (net (code "73") (name "unconnected-(JP9-Pad10)") (class "Default")
      (node (ref "JP9") (pin "10") (pinfunction "10_10") (pintype "passive"))
    )
  )
)
